# lm27313_5_12.net
KiCad netlist of a schematic drawn in Altium Designer
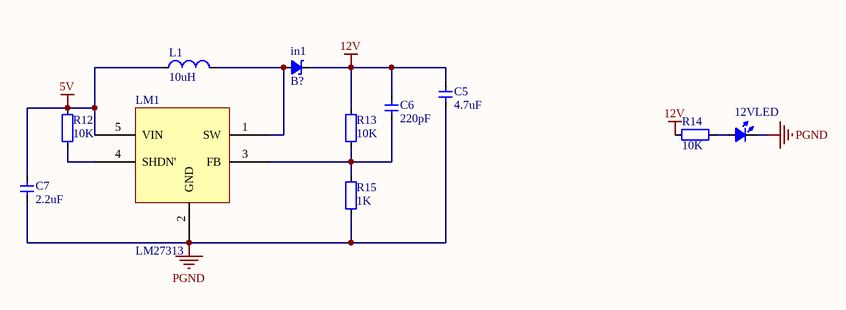
[diagram p0: lm27313_5_12.SchDoc]

(export (version "E")
  (design (tool "Eeschema 10.0.6"))
  (components
    (comp (ref "12VLED")
      (value "LED_0805")
      (footprint "LED_0805_GREEN")
      (description "LED")
      (libsource (lib "SCH_Active") (part "LED_0603"))
    )
    (comp (ref "C5")
      (value "4.7uF")
      (footprint "CAP_0603")
      (description "Capacitor")
      (fields (field (name "Comment") "Cap_0603"))
      (libsource (lib "Integrated_Library") (part "Cap_0603"))
    )
    (comp (ref "C6")
      (value "220pF")
      (footprint "CAP_0603")
      (description "Capacitor")
      (fields (field (name "Comment") "Cap_0603"))
      (libsource (lib "Integrated_Library") (part "Cap_0603"))
    )
    (comp (ref "C7")
      (value "2.2uF")
      (footprint "CAP_0603")
      (description "Capacitor")
      (fields (field (name "Comment") "Cap_0603"))
      (libsource (lib "Integrated_Library") (part "Cap_0603"))
    )
    (comp (ref "in1")
      (value "B?")
      (footprint "PCB_ActiveDIO:SOD-123")
      (description "Diode")
      (fields (field (name "Comment") "SchottkyDiode_SOD123"))
      (libsource (lib "SCH_Active") (part "SchottkyDiode_SOD123"))
    )
    (comp (ref "L1")
      (value "10uH")
      (footprint "indmm5x2_2_2")
      (description "Inductor")
      (libsource (lib "Integrated_Library") (part "Ind_0603"))
    )
    (comp (ref "LM1")
      (value "LM27313")
      (footprint "SOT23-5")
      (libsource (lib "Integrated_Library") (part "LM27313"))
    )
    (comp (ref "R12")
      (value "10K")
      (footprint "RES_0603")
      (description "Resistor")
      (fields (field (name "Comment") "Res_0603"))
      (libsource (lib "Integrated_Library") (part "Res_0603"))
    )
    (comp (ref "R13")
      (value "10K")
      (footprint "RES_0603")
      (description "Resistor")
      (fields (field (name "Comment") "Res_0603"))
      (libsource (lib "Integrated_Library") (part "Res_0603"))
    )
    (comp (ref "R14")
      (value "10K")
      (footprint "RES_0603")
      (description "Resistor")
      (fields (field (name "Comment") "Res_0603"))
      (libsource (lib "") (part "Res_0603_1"))
    )
    (comp (ref "R15")
      (value "1K")
      (footprint "RES_0603")
      (description "Resistor")
      (fields (field (name "Comment") "Res_0603"))
      (libsource (lib "Integrated_Library") (part "Res_0603"))
    )
  )
  (nets
    (net (code "1") (name "5V") (class "Default")
      (node (ref "C7") (pin "2") (pinfunction "2_2") (pintype "passive"))
      (node (ref "L1") (pin "1") (pinfunction "1_1") (pintype "passive"))
      (node (ref "LM1") (pin "5") (pinfunction "VIN_5") (pintype "passive"))
      (node (ref "R12") (pin "2") (pinfunction "2_2") (pintype "passive"))
    )
    (net (code "2") (name "12V") (class "Default")
      (node (ref "C5") (pin "2") (pinfunction "2_2") (pintype "passive"))
      (node (ref "C6") (pin "2") (pinfunction "2_2") (pintype "passive"))
      (node (ref "R13") (pin "2") (pinfunction "2_2") (pintype "passive"))
      (node (ref "R14") (pin "1") (pinfunction "1_1") (pintype "passive"))
      (node (ref "in1") (pin "2") (pinfunction "K_2") (pintype "passive"))
    )
    (net (code "3") (name "Net-(12VLED-A)") (class "Default")
      (node (ref "12VLED") (pin "1") (pinfunction "A_1") (pintype "passive"))
      (node (ref "R14") (pin "2") (pinfunction "2_2") (pintype "passive"))
    )
    (net (code "4") (name "Net-(LM1-FB)") (class "Default")
      (node (ref "C6") (pin "1") (pinfunction "1_1") (pintype "passive"))
      (node (ref "LM1") (pin "3") (pinfunction "FB_3") (pintype "passive"))
      (node (ref "R13") (pin "1") (pinfunction "1_1") (pintype "passive"))
      (node (ref "R15") (pin "2") (pinfunction "2_2") (pintype "passive"))
    )
    (net (code "5") (name "Net-(LM1-SHDN')") (class "Default")
      (node (ref "LM1") (pin "4") (pinfunction "SHDN'_4") (pintype "passive"))
      (node (ref "R12") (pin "1") (pinfunction "1_1") (pintype "passive"))
    )
    (net (code "6") (name "Net-(LM1-SW)") (class "Default")
      (node (ref "L1") (pin "2") (pinfunction "2_2") (pintype "passive"))
      (node (ref "LM1") (pin "1") (pinfunction "SW_1") (pintype "passive"))
      (node (ref "in1") (pin "1") (pinfunction "A_1") (pintype "passive"))
    )
    (net (code "7") (name "PGND") (class "Default")
      (node (ref "12VLED") (pin "2") (pinfunction "K_2") (pintype "passive"))
      (node (ref "C5") (pin "1") (pinfunction "1_1") (pintype "passive"))
      (node (ref "C7") (pin "1") (pinfunction "1_1") (pintype "passive"))
      (node (ref "LM1") (pin "2") (pinfunction "GND_2") (pintype "passive"))
      (node (ref "R15") (pin "1") (pinfunction "1_1") (pintype "passive"))
    )
  )
)
